# MX4-7-9.net
KiCad netlist of a schematic drawn in EAGLE
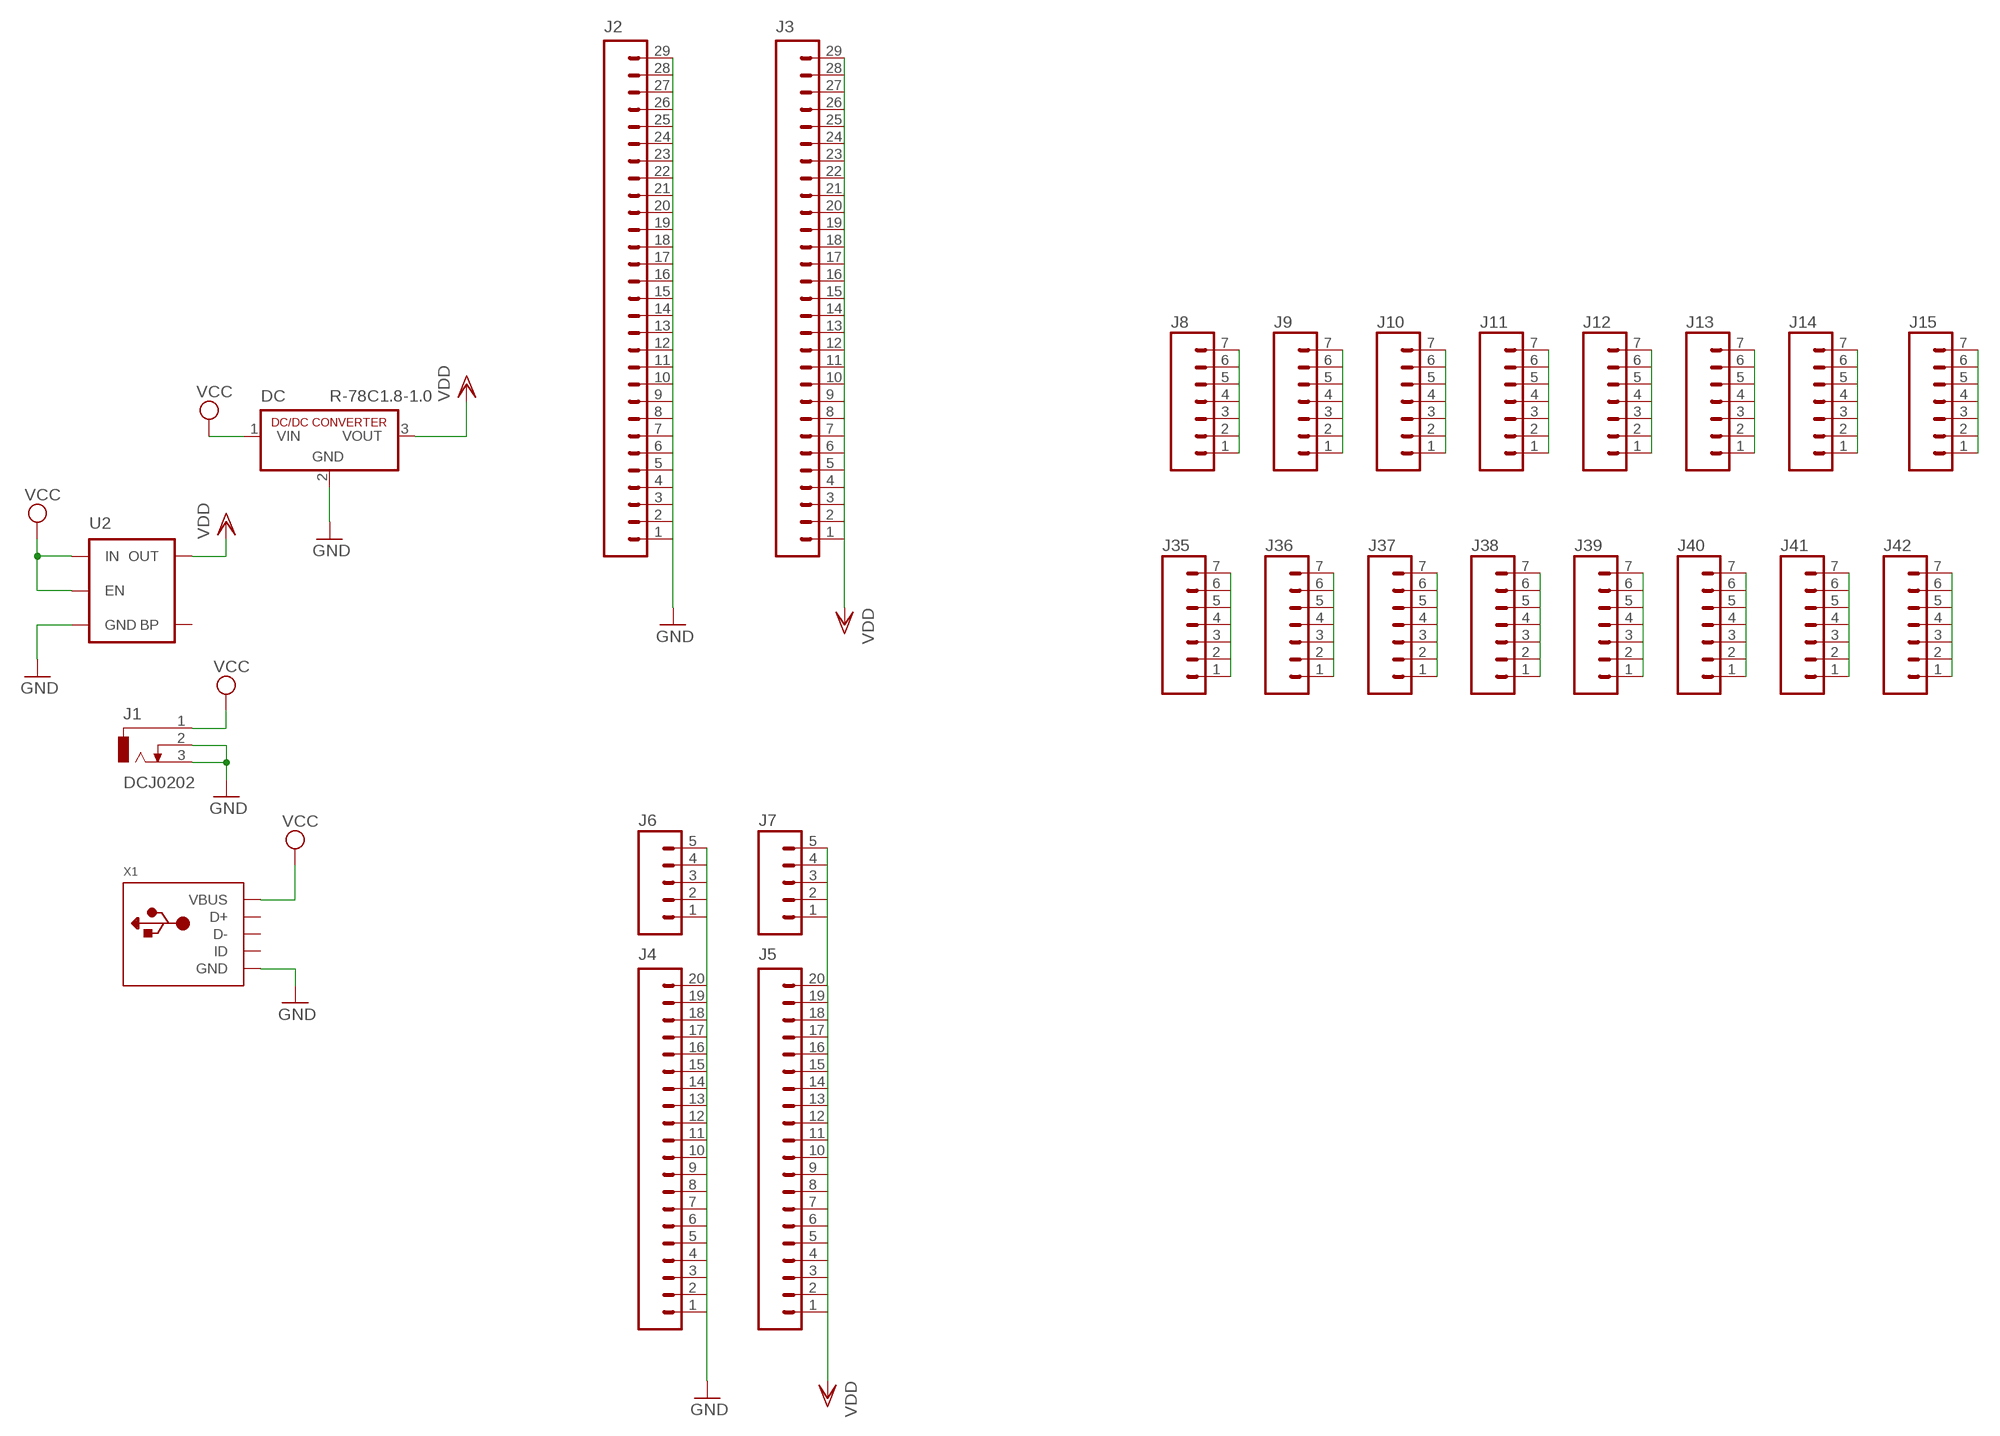
[diagram p0: schematic, sheet 1, part 1 of 2]
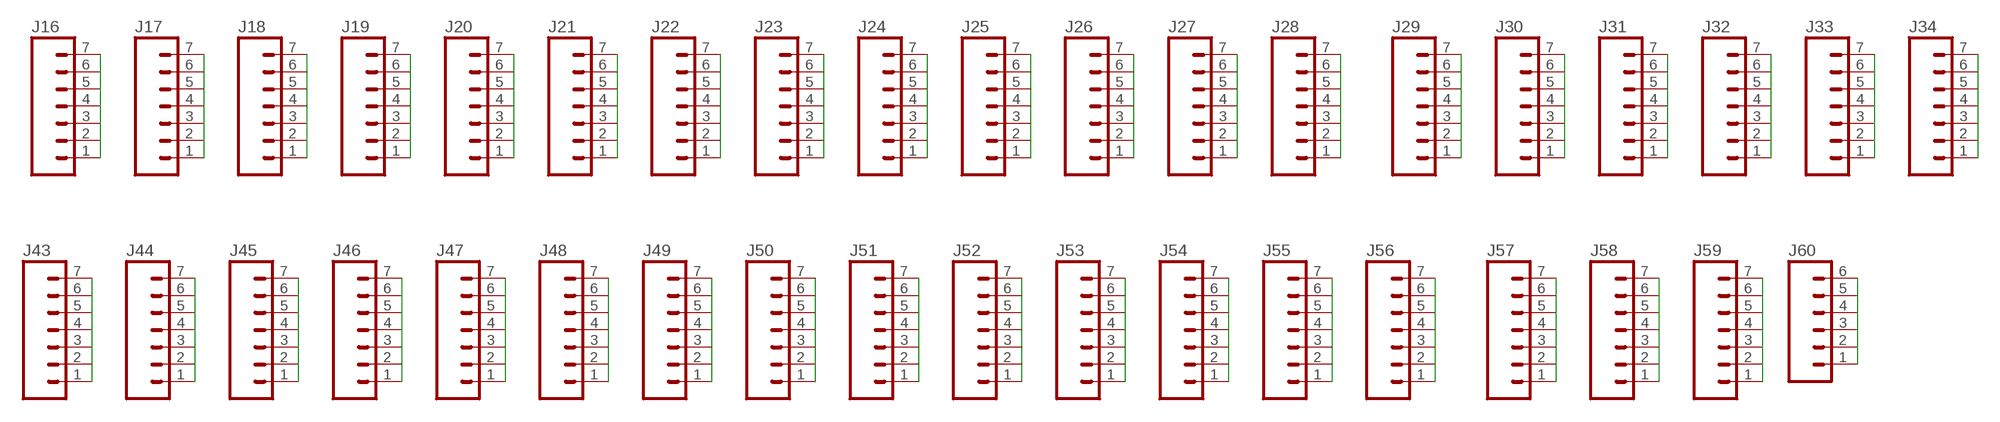
[diagram p1: schematic, sheet 1, part 2 of 2]

(export (version "E")
  (design (tool "Eeschema 10.0.6"))
  (components
    (comp (ref "DC")
      (value "R-78C1.8-1.0")
      (footprint "eagle-import:SIP3")
      (libsource (lib "eagle-import") (part "R-78C-1.01.8"))
    )
    (comp (ref "J1")
      (value "DCJ0202")
      (footprint "eagle-import:DCJ0202")
      (libsource (lib "eagle-import") (part "DCJ0202"))
    )
    (comp (ref "J2")
      (value "M29NO_SILK")
      (footprint "eagle-import:1X29_NO_SILK")
      (libsource (lib "eagle-import") (part "M29NO_SILK"))
    )
    (comp (ref "J3")
      (value "M29NO_SILK")
      (footprint "eagle-import:1X29_NO_SILK")
      (libsource (lib "eagle-import") (part "M29NO_SILK"))
    )
    (comp (ref "J4")
      (value "M20NO_SILK_KIT")
      (footprint "eagle-import:1X20_NO_SILK_KIT")
      (libsource (lib "eagle-import") (part "M20NO_SILK_KIT"))
    )
    (comp (ref "J5")
      (value "M20NO_SILK_KIT")
      (footprint "eagle-import:1X20_NO_SILK_KIT")
      (libsource (lib "eagle-import") (part "M20NO_SILK_KIT"))
    )
    (comp (ref "J6")
      (value "M05NO_SILK")
      (footprint "eagle-import:1X05_NO_SILK")
      (libsource (lib "eagle-import") (part "M05NO_SILK"))
    )
    (comp (ref "J7")
      (value "M05NO_SILK")
      (footprint "eagle-import:1X05_NO_SILK")
      (libsource (lib "eagle-import") (part "M05NO_SILK"))
    )
    (comp (ref "J8")
      (value "M07NO_SILK")
      (footprint "eagle-import:1X07_NO_SILK")
      (libsource (lib "eagle-import") (part "M07NO_SILK"))
    )
    (comp (ref "J9")
      (value "M07NO_SILK")
      (footprint "eagle-import:1X07_NO_SILK")
      (libsource (lib "eagle-import") (part "M07NO_SILK"))
    )
    (comp (ref "J10")
      (value "M07NO_SILK")
      (footprint "eagle-import:1X07_NO_SILK")
      (libsource (lib "eagle-import") (part "M07NO_SILK"))
    )
    (comp (ref "J11")
      (value "M07NO_SILK")
      (footprint "eagle-import:1X07_NO_SILK")
      (libsource (lib "eagle-import") (part "M07NO_SILK"))
    )
    (comp (ref "J12")
      (value "M07NO_SILK")
      (footprint "eagle-import:1X07_NO_SILK")
      (libsource (lib "eagle-import") (part "M07NO_SILK"))
    )
    (comp (ref "J13")
      (value "M07NO_SILK")
      (footprint "eagle-import:1X07_NO_SILK")
      (libsource (lib "eagle-import") (part "M07NO_SILK"))
    )
    (comp (ref "J14")
      (value "M07NO_SILK")
      (footprint "eagle-import:1X07_NO_SILK")
      (libsource (lib "eagle-import") (part "M07NO_SILK"))
    )
    (comp (ref "J15")
      (value "M07NO_SILK")
      (footprint "eagle-import:1X07_NO_SILK")
      (libsource (lib "eagle-import") (part "M07NO_SILK"))
    )
    (comp (ref "J16")
      (value "M07NO_SILK")
      (footprint "eagle-import:1X07_NO_SILK")
      (libsource (lib "eagle-import") (part "M07NO_SILK"))
    )
    (comp (ref "J17")
      (value "M07NO_SILK")
      (footprint "eagle-import:1X07_NO_SILK")
      (libsource (lib "eagle-import") (part "M07NO_SILK"))
    )
    (comp (ref "J18")
      (value "M07NO_SILK")
      (footprint "eagle-import:1X07_NO_SILK")
      (libsource (lib "eagle-import") (part "M07NO_SILK"))
    )
    (comp (ref "J19")
      (value "M07NO_SILK")
      (footprint "eagle-import:1X07_NO_SILK")
      (libsource (lib "eagle-import") (part "M07NO_SILK"))
    )
    (comp (ref "J20")
      (value "M07NO_SILK")
      (footprint "eagle-import:1X07_NO_SILK")
      (libsource (lib "eagle-import") (part "M07NO_SILK"))
    )
    (comp (ref "J21")
      (value "M07NO_SILK")
      (footprint "eagle-import:1X07_NO_SILK")
      (libsource (lib "eagle-import") (part "M07NO_SILK"))
    )
    (comp (ref "J22")
      (value "M07NO_SILK")
      (footprint "eagle-import:1X07_NO_SILK")
      (libsource (lib "eagle-import") (part "M07NO_SILK"))
    )
    (comp (ref "J23")
      (value "M07NO_SILK")
      (footprint "eagle-import:1X07_NO_SILK")
      (libsource (lib "eagle-import") (part "M07NO_SILK"))
    )
    (comp (ref "J24")
      (value "M07NO_SILK")
      (footprint "eagle-import:1X07_NO_SILK")
      (libsource (lib "eagle-import") (part "M07NO_SILK"))
    )
    (comp (ref "J25")
      (value "M07NO_SILK")
      (footprint "eagle-import:1X07_NO_SILK")
      (libsource (lib "eagle-import") (part "M07NO_SILK"))
    )
    (comp (ref "J26")
      (value "M07NO_SILK")
      (footprint "eagle-import:1X07_NO_SILK")
      (libsource (lib "eagle-import") (part "M07NO_SILK"))
    )
    (comp (ref "J27")
      (value "M07NO_SILK")
      (footprint "eagle-import:1X07_NO_SILK")
      (libsource (lib "eagle-import") (part "M07NO_SILK"))
    )
    (comp (ref "J28")
      (value "M07NO_SILK")
      (footprint "eagle-import:1X07_NO_SILK")
      (libsource (lib "eagle-import") (part "M07NO_SILK"))
    )
    (comp (ref "J29")
      (value "M07NO_SILK")
      (footprint "eagle-import:1X07_NO_SILK")
      (libsource (lib "eagle-import") (part "M07NO_SILK"))
    )
    (comp (ref "J30")
      (value "M07NO_SILK")
      (footprint "eagle-import:1X07_NO_SILK")
      (libsource (lib "eagle-import") (part "M07NO_SILK"))
    )
    (comp (ref "J31")
      (value "M07NO_SILK")
      (footprint "eagle-import:1X07_NO_SILK")
      (libsource (lib "eagle-import") (part "M07NO_SILK"))
    )
    (comp (ref "J32")
      (value "M07NO_SILK")
      (footprint "eagle-import:1X07_NO_SILK")
      (libsource (lib "eagle-import") (part "M07NO_SILK"))
    )
    (comp (ref "J33")
      (value "M07NO_SILK")
      (footprint "eagle-import:1X07_NO_SILK")
      (libsource (lib "eagle-import") (part "M07NO_SILK"))
    )
    (comp (ref "J34")
      (value "M07NO_SILK")
      (footprint "eagle-import:1X07_NO_SILK")
      (libsource (lib "eagle-import") (part "M07NO_SILK"))
    )
    (comp (ref "J35")
      (value "M07NO_SILK")
      (footprint "eagle-import:1X07_NO_SILK")
      (libsource (lib "eagle-import") (part "M07NO_SILK"))
    )
    (comp (ref "J36")
      (value "M07NO_SILK")
      (footprint "eagle-import:1X07_NO_SILK")
      (libsource (lib "eagle-import") (part "M07NO_SILK"))
    )
    (comp (ref "J37")
      (value "M07NO_SILK")
      (footprint "eagle-import:1X07_NO_SILK")
      (libsource (lib "eagle-import") (part "M07NO_SILK"))
    )
    (comp (ref "J38")
      (value "M07NO_SILK")
      (footprint "eagle-import:1X07_NO_SILK")
      (libsource (lib "eagle-import") (part "M07NO_SILK"))
    )
    (comp (ref "J39")
      (value "M07NO_SILK")
      (footprint "eagle-import:1X07_NO_SILK")
      (libsource (lib "eagle-import") (part "M07NO_SILK"))
    )
    (comp (ref "J40")
      (value "M07NO_SILK")
      (footprint "eagle-import:1X07_NO_SILK")
      (libsource (lib "eagle-import") (part "M07NO_SILK"))
    )
    (comp (ref "J41")
      (value "M07NO_SILK")
      (footprint "eagle-import:1X07_NO_SILK")
      (libsource (lib "eagle-import") (part "M07NO_SILK"))
    )
    (comp (ref "J42")
      (value "M07NO_SILK")
      (footprint "eagle-import:1X07_NO_SILK")
      (libsource (lib "eagle-import") (part "M07NO_SILK"))
    )
    (comp (ref "J43")
      (value "M07NO_SILK")
      (footprint "eagle-import:1X07_NO_SILK")
      (libsource (lib "eagle-import") (part "M07NO_SILK"))
    )
    (comp (ref "J44")
      (value "M07NO_SILK")
      (footprint "eagle-import:1X07_NO_SILK")
      (libsource (lib "eagle-import") (part "M07NO_SILK"))
    )
    (comp (ref "J45")
      (value "M07NO_SILK")
      (footprint "eagle-import:1X07_NO_SILK")
      (libsource (lib "eagle-import") (part "M07NO_SILK"))
    )
    (comp (ref "J46")
      (value "M07NO_SILK")
      (footprint "eagle-import:1X07_NO_SILK")
      (libsource (lib "eagle-import") (part "M07NO_SILK"))
    )
    (comp (ref "J47")
      (value "M07NO_SILK")
      (footprint "eagle-import:1X07_NO_SILK")
      (libsource (lib "eagle-import") (part "M07NO_SILK"))
    )
    (comp (ref "J48")
      (value "M07NO_SILK")
      (footprint "eagle-import:1X07_NO_SILK")
      (libsource (lib "eagle-import") (part "M07NO_SILK"))
    )
    (comp (ref "J49")
      (value "M07NO_SILK")
      (footprint "eagle-import:1X07_NO_SILK")
      (libsource (lib "eagle-import") (part "M07NO_SILK"))
    )
    (comp (ref "J50")
      (value "M07NO_SILK")
      (footprint "eagle-import:1X07_NO_SILK")
      (libsource (lib "eagle-import") (part "M07NO_SILK"))
    )
    (comp (ref "J51")
      (value "M07NO_SILK")
      (footprint "eagle-import:1X07_NO_SILK")
      (libsource (lib "eagle-import") (part "M07NO_SILK"))
    )
    (comp (ref "J52")
      (value "M07NO_SILK")
      (footprint "eagle-import:1X07_NO_SILK")
      (libsource (lib "eagle-import") (part "M07NO_SILK"))
    )
    (comp (ref "J53")
      (value "M07NO_SILK")
      (footprint "eagle-import:1X07_NO_SILK")
      (libsource (lib "eagle-import") (part "M07NO_SILK"))
    )
    (comp (ref "J54")
      (value "M07NO_SILK")
      (footprint "eagle-import:1X07_NO_SILK")
      (libsource (lib "eagle-import") (part "M07NO_SILK"))
    )
    (comp (ref "J55")
      (value "M07NO_SILK")
      (footprint "eagle-import:1X07_NO_SILK")
      (libsource (lib "eagle-import") (part "M07NO_SILK"))
    )
    (comp (ref "J56")
      (value "M07NO_SILK")
      (footprint "eagle-import:1X07_NO_SILK")
      (libsource (lib "eagle-import") (part "M07NO_SILK"))
    )
    (comp (ref "J57")
      (value "M07NO_SILK")
      (footprint "eagle-import:1X07_NO_SILK")
      (libsource (lib "eagle-import") (part "M07NO_SILK"))
    )
    (comp (ref "J58")
      (value "M07NO_SILK")
      (footprint "eagle-import:1X07_NO_SILK")
      (libsource (lib "eagle-import") (part "M07NO_SILK"))
    )
    (comp (ref "J59")
      (value "M07NO_SILK")
      (footprint "eagle-import:1X07_NO_SILK")
      (libsource (lib "eagle-import") (part "M07NO_SILK"))
    )
    (comp (ref "J60")
      (value "M06NO_SILK_FEMALE_PTH")
      (footprint "eagle-import:1X06_NO_SILK")
      (libsource (lib "eagle-import") (part "M06NO_SILK_FEMALE_PTH"))
    )
    (comp (ref "U2")
      (value "MIC52053.3V")
      (footprint "eagle-import:SOT23-5")
      (libsource (lib "eagle-import") (part "MIC52053.3V"))
    )
    (comp (ref "X1")
      (value "USBMICRO_20329")
      (footprint "eagle-import:4UCONN_20329")
      (libsource (lib "eagle-import") (part "USBMICRO_20329"))
    )
  )
  (nets
    (net (code "1") (name "GND") (class "Default")
      (node (ref "DC") (pin "2") (pinfunction "GND_2") (pintype "passive"))
      (node (ref "J1") (pin "2") (pinfunction "2_2") (pintype "passive"))
      (node (ref "J1") (pin "3") (pinfunction "3_3") (pintype "passive"))
      (node (ref "J2") (pin "1") (pinfunction "1_1") (pintype "passive"))
      (node (ref "J2") (pin "10") (pinfunction "10_10") (pintype "passive"))
      (node (ref "J2") (pin "11") (pinfunction "11_11") (pintype "passive"))
      (node (ref "J2") (pin "12") (pinfunction "12_12") (pintype "passive"))
      (node (ref "J2") (pin "13") (pinfunction "13_13") (pintype "passive"))
      (node (ref "J2") (pin "14") (pinfunction "14_14") (pintype "passive"))
      (node (ref "J2") (pin "15") (pinfunction "15_15") (pintype "passive"))
      (node (ref "J2") (pin "16") (pinfunction "16_16") (pintype "passive"))
      (node (ref "J2") (pin "17") (pinfunction "17_17") (pintype "passive"))
      (node (ref "J2") (pin "18") (pinfunction "18_18") (pintype "passive"))
      (node (ref "J2") (pin "19") (pinfunction "19_19") (pintype "passive"))
      (node (ref "J2") (pin "2") (pinfunction "2_2") (pintype "passive"))
      (node (ref "J2") (pin "20") (pinfunction "20_20") (pintype "passive"))
      (node (ref "J2") (pin "21") (pinfunction "21_21") (pintype "passive"))
      (node (ref "J2") (pin "22") (pinfunction "22_22") (pintype "passive"))
      (node (ref "J2") (pin "23") (pinfunction "23_23") (pintype "passive"))
      (node (ref "J2") (pin "24") (pinfunction "24_24") (pintype "passive"))
      (node (ref "J2") (pin "25") (pinfunction "25_25") (pintype "passive"))
      (node (ref "J2") (pin "26") (pinfunction "26_26") (pintype "passive"))
      (node (ref "J2") (pin "27") (pinfunction "27_27") (pintype "passive"))
      (node (ref "J2") (pin "28") (pinfunction "28_28") (pintype "passive"))
      (node (ref "J2") (pin "29") (pinfunction "29_29") (pintype "passive"))
      (node (ref "J2") (pin "3") (pinfunction "3_3") (pintype "passive"))
      (node (ref "J2") (pin "4") (pinfunction "4_4") (pintype "passive"))
      (node (ref "J2") (pin "5") (pinfunction "5_5") (pintype "passive"))
      (node (ref "J2") (pin "6") (pinfunction "6_6") (pintype "passive"))
      (node (ref "J2") (pin "7") (pinfunction "7_7") (pintype "passive"))
      (node (ref "J2") (pin "8") (pinfunction "8_8") (pintype "passive"))
      (node (ref "J2") (pin "9") (pinfunction "9_9") (pintype "passive"))
      (node (ref "J4") (pin "1") (pinfunction "1_1") (pintype "passive"))
      (node (ref "J4") (pin "10") (pinfunction "10_10") (pintype "passive"))
      (node (ref "J4") (pin "11") (pinfunction "11_11") (pintype "passive"))
      (node (ref "J4") (pin "12") (pinfunction "12_12") (pintype "passive"))
      (node (ref "J4") (pin "13") (pinfunction "13_13") (pintype "passive"))
      (node (ref "J4") (pin "14") (pinfunction "14_14") (pintype "passive"))
      (node (ref "J4") (pin "15") (pinfunction "15_15") (pintype "passive"))
      (node (ref "J4") (pin "16") (pinfunction "16_16") (pintype "passive"))
      (node (ref "J4") (pin "17") (pinfunction "17_17") (pintype "passive"))
      (node (ref "J4") (pin "18") (pinfunction "18_18") (pintype "passive"))
      (node (ref "J4") (pin "19") (pinfunction "19_19") (pintype "passive"))
      (node (ref "J4") (pin "2") (pinfunction "2_2") (pintype "passive"))
      (node (ref "J4") (pin "20") (pinfunction "20_20") (pintype "passive"))
      (node (ref "J4") (pin "3") (pinfunction "3_3") (pintype "passive"))
      (node (ref "J4") (pin "4") (pinfunction "4_4") (pintype "passive"))
      (node (ref "J4") (pin "5") (pinfunction "5_5") (pintype "passive"))
      (node (ref "J4") (pin "6") (pinfunction "6_6") (pintype "passive"))
      (node (ref "J4") (pin "7") (pinfunction "7_7") (pintype "passive"))
      (node (ref "J4") (pin "8") (pinfunction "8_8") (pintype "passive"))
      (node (ref "J4") (pin "9") (pinfunction "9_9") (pintype "passive"))
      (node (ref "J6") (pin "1") (pinfunction "1_1") (pintype "passive"))
      (node (ref "J6") (pin "2") (pinfunction "2_2") (pintype "passive"))
      (node (ref "J6") (pin "3") (pinfunction "3_3") (pintype "passive"))
      (node (ref "J6") (pin "4") (pinfunction "4_4") (pintype "passive"))
      (node (ref "J6") (pin "5") (pinfunction "5_5") (pintype "passive"))
      (node (ref "U2") (pin "2") (pinfunction "GND_2") (pintype "input"))
      (node (ref "X1") (pin "BASE@1") (pinfunction "GND_BASE@1") (pintype "power_in"))
      (node (ref "X1") (pin "BASE@2") (pinfunction "GND_BASE@2") (pintype "power_in"))
      (node (ref "X1") (pin "GND") (pinfunction "GND_GND") (pintype "power_in"))
      (node (ref "X1") (pin "SPRT@1") (pinfunction "GND_SPRT@1") (pintype "power_in"))
      (node (ref "X1") (pin "SPRT@2") (pinfunction "GND_SPRT@2") (pintype "power_in"))
      (node (ref "X1") (pin "SPRT@3") (pinfunction "GND_SPRT@3") (pintype "power_in"))
      (node (ref "X1") (pin "SPRT@4") (pinfunction "GND_SPRT@4") (pintype "power_in"))
    )
    (net (code "2") (name "Net-(J8-Pad1)") (class "Default")
      (node (ref "J8") (pin "1") (pinfunction "1_1") (pintype "passive"))
      (node (ref "J8") (pin "2") (pinfunction "2_2") (pintype "passive"))
      (node (ref "J8") (pin "3") (pinfunction "3_3") (pintype "passive"))
      (node (ref "J8") (pin "4") (pinfunction "4_4") (pintype "passive"))
      (node (ref "J8") (pin "5") (pinfunction "5_5") (pintype "passive"))
      (node (ref "J8") (pin "6") (pinfunction "6_6") (pintype "passive"))
      (node (ref "J8") (pin "7") (pinfunction "7_7") (pintype "passive"))
    )
    (net (code "3") (name "Net-(J9-Pad1)") (class "Default")
      (node (ref "J9") (pin "1") (pinfunction "1_1") (pintype "passive"))
      (node (ref "J9") (pin "2") (pinfunction "2_2") (pintype "passive"))
      (node (ref "J9") (pin "3") (pinfunction "3_3") (pintype "passive"))
      (node (ref "J9") (pin "4") (pinfunction "4_4") (pintype "passive"))
      (node (ref "J9") (pin "5") (pinfunction "5_5") (pintype "passive"))
      (node (ref "J9") (pin "6") (pinfunction "6_6") (pintype "passive"))
      (node (ref "J9") (pin "7") (pinfunction "7_7") (pintype "passive"))
    )
    (net (code "4") (name "Net-(J10-Pad1)") (class "Default")
      (node (ref "J10") (pin "1") (pinfunction "1_1") (pintype "passive"))
      (node (ref "J10") (pin "2") (pinfunction "2_2") (pintype "passive"))
      (node (ref "J10") (pin "3") (pinfunction "3_3") (pintype "passive"))
      (node (ref "J10") (pin "4") (pinfunction "4_4") (pintype "passive"))
      (node (ref "J10") (pin "5") (pinfunction "5_5") (pintype "passive"))
      (node (ref "J10") (pin "6") (pinfunction "6_6") (pintype "passive"))
      (node (ref "J10") (pin "7") (pinfunction "7_7") (pintype "passive"))
    )
    (net (code "5") (name "Net-(J11-Pad1)") (class "Default")
      (node (ref "J11") (pin "1") (pinfunction "1_1") (pintype "passive"))
      (node (ref "J11") (pin "2") (pinfunction "2_2") (pintype "passive"))
      (node (ref "J11") (pin "3") (pinfunction "3_3") (pintype "passive"))
      (node (ref "J11") (pin "4") (pinfunction "4_4") (pintype "passive"))
      (node (ref "J11") (pin "5") (pinfunction "5_5") (pintype "passive"))
      (node (ref "J11") (pin "6") (pinfunction "6_6") (pintype "passive"))
      (node (ref "J11") (pin "7") (pinfunction "7_7") (pintype "passive"))
    )
    (net (code "6") (name "Net-(J12-Pad1)") (class "Default")
      (node (ref "J12") (pin "1") (pinfunction "1_1") (pintype "passive"))
      (node (ref "J12") (pin "2") (pinfunction "2_2") (pintype "passive"))
      (node (ref "J12") (pin "3") (pinfunction "3_3") (pintype "passive"))
      (node (ref "J12") (pin "4") (pinfunction "4_4") (pintype "passive"))
      (node (ref "J12") (pin "5") (pinfunction "5_5") (pintype "passive"))
      (node (ref "J12") (pin "6") (pinfunction "6_6") (pintype "passive"))
      (node (ref "J12") (pin "7") (pinfunction "7_7") (pintype "passive"))
    )
    (net (code "7") (name "Net-(J13-Pad1)") (class "Default")
      (node (ref "J13") (pin "1") (pinfunction "1_1") (pintype "passive"))
      (node (ref "J13") (pin "2") (pinfunction "2_2") (pintype "passive"))
      (node (ref "J13") (pin "3") (pinfunction "3_3") (pintype "passive"))
      (node (ref "J13") (pin "4") (pinfunction "4_4") (pintype "passive"))
      (node (ref "J13") (pin "5") (pinfunction "5_5") (pintype "passive"))
      (node (ref "J13") (pin "6") (pinfunction "6_6") (pintype "passive"))
      (node (ref "J13") (pin "7") (pinfunction "7_7") (pintype "passive"))
    )
    (net (code "8") (name "Net-(J14-Pad1)") (class "Default")
      (node (ref "J14") (pin "1") (pinfunction "1_1") (pintype "passive"))
      (node (ref "J14") (pin "2") (pinfunction "2_2") (pintype "passive"))
      (node (ref "J14") (pin "3") (pinfunction "3_3") (pintype "passive"))
      (node (ref "J14") (pin "4") (pinfunction "4_4") (pintype "passive"))
      (node (ref "J14") (pin "5") (pinfunction "5_5") (pintype "passive"))
      (node (ref "J14") (pin "6") (pinfunction "6_6") (pintype "passive"))
      (node (ref "J14") (pin "7") (pinfunction "7_7") (pintype "passive"))
    )
    (net (code "9") (name "Net-(J15-Pad1)") (class "Default")
      (node (ref "J15") (pin "1") (pinfunction "1_1") (pintype "passive"))
      (node (ref "J15") (pin "2") (pinfunction "2_2") (pintype "passive"))
      (node (ref "J15") (pin "3") (pinfunction "3_3") (pintype "passive"))
      (node (ref "J15") (pin "4") (pinfunction "4_4") (pintype "passive"))
      (node (ref "J15") (pin "5") (pinfunction "5_5") (pintype "passive"))
      (node (ref "J15") (pin "6") (pinfunction "6_6") (pintype "passive"))
      (node (ref "J15") (pin "7") (pinfunction "7_7") (pintype "passive"))
    )
    (net (code "10") (name "Net-(J16-Pad1)") (class "Default")
      (node (ref "J16") (pin "1") (pinfunction "1_1") (pintype "passive"))
      (node (ref "J16") (pin "2") (pinfunction "2_2") (pintype "passive"))
      (node (ref "J16") (pin "3") (pinfunction "3_3") (pintype "passive"))
      (node (ref "J16") (pin "4") (pinfunction "4_4") (pintype "passive"))
      (node (ref "J16") (pin "5") (pinfunction "5_5") (pintype "passive"))
      (node (ref "J16") (pin "6") (pinfunction "6_6") (pintype "passive"))
      (node (ref "J16") (pin "7") (pinfunction "7_7") (pintype "passive"))
    )
    (net (code "11") (name "Net-(J17-Pad1)") (class "Default")
      (node (ref "J17") (pin "1") (pinfunction "1_1") (pintype "passive"))
      (node (ref "J17") (pin "2") (pinfunction "2_2") (pintype "passive"))
      (node (ref "J17") (pin "3") (pinfunction "3_3") (pintype "passive"))
      (node (ref "J17") (pin "4") (pinfunction "4_4") (pintype "passive"))
      (node (ref "J17") (pin "5") (pinfunction "5_5") (pintype "passive"))
      (node (ref "J17") (pin "6") (pinfunction "6_6") (pintype "passive"))
      (node (ref "J17") (pin "7") (pinfunction "7_7") (pintype "passive"))
    )
    (net (code "12") (name "Net-(J18-Pad1)") (class "Default")
      (node (ref "J18") (pin "1") (pinfunction "1_1") (pintype "passive"))
      (node (ref "J18") (pin "2") (pinfunction "2_2") (pintype "passive"))
      (node (ref "J18") (pin "3") (pinfunction "3_3") (pintype "passive"))
      (node (ref "J18") (pin "4") (pinfunction "4_4") (pintype "passive"))
      (node (ref "J18") (pin "5") (pinfunction "5_5") (pintype "passive"))
      (node (ref "J18") (pin "6") (pinfunction "6_6") (pintype "passive"))
      (node (ref "J18") (pin "7") (pinfunction "7_7") (pintype "passive"))
    )
    (net (code "13") (name "Net-(J19-Pad1)") (class "Default")
      (node (ref "J19") (pin "1") (pinfunction "1_1") (pintype "passive"))
      (node (ref "J19") (pin "2") (pinfunction "2_2") (pintype "passive"))
      (node (ref "J19") (pin "3") (pinfunction "3_3") (pintype "passive"))
      (node (ref "J19") (pin "4") (pinfunction "4_4") (pintype "passive"))
      (node (ref "J19") (pin "5") (pinfunction "5_5") (pintype "passive"))
      (node (ref "J19") (pin "6") (pinfunction "6_6") (pintype "passive"))
      (node (ref "J19") (pin "7") (pinfunction "7_7") (pintype "passive"))
    )
    (net (code "14") (name "Net-(J20-Pad1)") (class "Default")
      (node (ref "J20") (pin "1") (pinfunction "1_1") (pintype "passive"))
      (node (ref "J20") (pin "2") (pinfunction "2_2") (pintype "passive"))
      (node (ref "J20") (pin "3") (pinfunction "3_3") (pintype "passive"))
      (node (ref "J20") (pin "4") (pinfunction "4_4") (pintype "passive"))
      (node (ref "J20") (pin "5") (pinfunction "5_5") (pintype "passive"))
      (node (ref "J20") (pin "6") (pinfunction "6_6") (pintype "passive"))
      (node (ref "J20") (pin "7") (pinfunction "7_7") (pintype "passive"))
    )
    (net (code "15") (name "Net-(J21-Pad1)") (class "Default")
      (node (ref "J21") (pin "1") (pinfunction "1_1") (pintype "passive"))
      (node (ref "J21") (pin "2") (pinfunction "2_2") (pintype "passive"))
      (node (ref "J21") (pin "3") (pinfunction "3_3") (pintype "passive"))
      (node (ref "J21") (pin "4") (pinfunction "4_4") (pintype "passive"))
      (node (ref "J21") (pin "5") (pinfunction "5_5") (pintype "passive"))
      (node (ref "J21") (pin "6") (pinfunction "6_6") (pintype "passive"))
      (node (ref "J21") (pin "7") (pinfunction "7_7") (pintype "passive"))
    )
    (net (code "16") (name "Net-(J22-Pad1)") (class "Default")
      (node (ref "J22") (pin "1") (pinfunction "1_1") (pintype "passive"))
      (node (ref "J22") (pin "2") (pinfunction "2_2") (pintype "passive"))
      (node (ref "J22") (pin "3") (pinfunction "3_3") (pintype "passive"))
      (node (ref "J22") (pin "4") (pinfunction "4_4") (pintype "passive"))
      (node (ref "J22") (pin "5") (pinfunction "5_5") (pintype "passive"))
      (node (ref "J22") (pin "6") (pinfunction "6_6") (pintype "passive"))
      (node (ref "J22") (pin "7") (pinfunction "7_7") (pintype "passive"))
    )
    (net (code "17") (name "Net-(J23-Pad1)") (class "Default")
      (node (ref "J23") (pin "1") (pinfunction "1_1") (pintype "passive"))
      (node (ref "J23") (pin "2") (pinfunction "2_2") (pintype "passive"))
      (node (ref "J23") (pin "3") (pinfunction "3_3") (pintype "passive"))
      (node (ref "J23") (pin "4") (pinfunction "4_4") (pintype "passive"))
      (node (ref "J23") (pin "5") (pinfunction "5_5") (pintype "passive"))
      (node (ref "J23") (pin "6") (pinfunction "6_6") (pintype "passive"))
      (node (ref "J23") (pin "7") (pinfunction "7_7") (pintype "passive"))
    )
    (net (code "18") (name "Net-(J24-Pad1)") (class "Default")
      (node (ref "J24") (pin "1") (pinfunction "1_1") (pintype "passive"))
      (node (ref "J24") (pin "2") (pinfunction "2_2") (pintype "passive"))
      (node (ref "J24") (pin "3") (pinfunction "3_3") (pintype "passive"))
      (node (ref "J24") (pin "4") (pinfunction "4_4") (pintype "passive"))
      (node (ref "J24") (pin "5") (pinfunction "5_5") (pintype "passive"))
      (node (ref "J24") (pin "6") (pinfunction "6_6") (pintype "passive"))
      (node (ref "J24") (pin "7") (pinfunction "7_7") (pintype "passive"))
    )
    (net (code "19") (name "Net-(J25-Pad1)") (class "Default")
      (node (ref "J25") (pin "1") (pinfunction "1_1") (pintype "passive"))
      (node (ref "J25") (pin "2") (pinfunction "2_2") (pintype "passive"))
      (node (ref "J25") (pin "3") (pinfunction "3_3") (pintype "passive"))
      (node (ref "J25") (pin "4") (pinfunction "4_4") (pintype "passive"))
      (node (ref "J25") (pin "5") (pinfunction "5_5") (pintype "passive"))
      (node (ref "J25") (pin "6") (pinfunction "6_6") (pintype "passive"))
      (node (ref "J25") (pin "7") (pinfunction "7_7") (pintype "passive"))
    )
    (net (code "20") (name "Net-(J26-Pad1)") (class "Default")
      (node (ref "J26") (pin "1") (pinfunction "1_1") (pintype "passive"))
      (node (ref "J26") (pin "2") (pinfunction "2_2") (pintype "passive"))
      (node (ref "J26") (pin "3") (pinfunction "3_3") (pintype "passive"))
      (node (ref "J26") (pin "4") (pinfunction "4_4") (pintype "passive"))
      (node (ref "J26") (pin "5") (pinfunction "5_5") (pintype "passive"))
      (node (ref "J26") (pin "6") (pinfunction "6_6") (pintype "passive"))
      (node (ref "J26") (pin "7") (pinfunction "7_7") (pintype "passive"))
    )
    (net (code "21") (name "Net-(J27-Pad1)") (class "Default")
      (node (ref "J27") (pin "1") (pinfunction "1_1") (pintype "passive"))
      (node (ref "J27") (pin "2") (pinfunction "2_2") (pintype "passive"))
      (node (ref "J27") (pin "3") (pinfunction "3_3") (pintype "passive"))
      (node (ref "J27") (pin "4") (pinfunction "4_4") (pintype "passive"))
      (node (ref "J27") (pin "5") (pinfunction "5_5") (pintype "passive"))
      (node (ref "J27") (pin "6") (pinfunction "6_6") (pintype "passive"))
      (node (ref "J27") (pin "7") (pinfunction "7_7") (pintype "passive"))
    )
    (net (code "22") (name "Net-(J28-Pad1)") (class "Default")
      (node (ref "J28") (pin "1") (pinfunction "1_1") (pintype "passive"))
      (node (ref "J28") (pin "2") (pinfunction "2_2") (pintype "passive"))
      (node (ref "J28") (pin "3") (pinfunction "3_3") (pintype "passive"))
      (node (ref "J28") (pin "4") (pinfunction "4_4") (pintype "passive"))
      (node (ref "J28") (pin "5") (pinfunction "5_5") (pintype "passive"))
      (node (ref "J28") (pin "6") (pinfunction "6_6") (pintype "passive"))
      (node (ref "J28") (pin "7") (pinfunction "7_7") (pintype "passive"))
    )
    (net (code "23") (name "Net-(J29-Pad1)") (class "Default")
      (node (ref "J29") (pin "1") (pinfunction "1_1") (pintype "passive"))
      (node (ref "J29") (pin "2") (pinfunction "2_2") (pintype "passive"))
      (node (ref "J29") (pin "3") (pinfunction "3_3") (pintype "passive"))
      (node (ref "J29") (pin "4") (pinfunction "4_4") (pintype "passive"))
      (node (ref "J29") (pin "5") (pinfunction "5_5") (pintype "passive"))
      (node (ref "J29") (pin "6") (pinfunction "6_6") (pintype "passive"))
      (node (ref "J29") (pin "7") (pinfunction "7_7") (pintype "passive"))
    )
    (net (code "24") (name "Net-(J30-Pad1)") (class "Default")
      (node (ref "J30") (pin "1") (pinfunction "1_1") (pintype "passive"))
      (node (ref "J30") (pin "2") (pinfunction "2_2") (pintype "passive"))
      (node (ref "J30") (pin "3") (pinfunction "3_3") (pintype "passive"))
      (node (ref "J30") (pin "4") (pinfunction "4_4") (pintype "passive"))
      (node (ref "J30") (pin "5") (pinfunction "5_5") (pintype "passive"))
      (node (ref "J30") (pin "6") (pinfunction "6_6") (pintype "passive"))
      (node (ref "J30") (pin "7") (pinfunction "7_7") (pintype "passive"))
    )
    (net (code "25") (name "Net-(J31-Pad1)") (class "Default")
      (node (ref "J31") (pin "1") (pinfunction "1_1") (pintype "passive"))
      (node (ref "J31") (pin "2") (pinfunction "2_2") (pintype "passive"))
      (node (ref "J31") (pin "3") (pinfunction "3_3") (pintype "passive"))
      (node (ref "J31") (pin "4") (pinfunction "4_4") (pintype "passive"))
      (node (ref "J31") (pin "5") (pinfunction "5_5") (pintype "passive"))
      (node (ref "J31") (pin "6") (pinfunction "6_6") (pintype "passive"))
      (node (ref "J31") (pin "7") (pinfunction "7_7") (pintype "passive"))
    )
    (net (code "26") (name "Net-(J32-Pad1)") (class "Default")
      (node (ref "J32") (pin "1") (pinfunction "1_1") (pintype "passive"))
      (node (ref "J32") (pin "2") (pinfunction "2_2") (pintype "passive"))
      (node (ref "J32") (pin "3") (pinfunction "3_3") (pintype "passive"))
      (node (ref "J32") (pin "4") (pinfunction "4_4") (pintype "passive"))
      (node (ref "J32") (pin "5") (pinfunction "5_5") (pintype "passive"))
      (node (ref "J32") (pin "6") (pinfunction "6_6") (pintype "passive"))
      (node (ref "J32") (pin "7") (pinfunction "7_7") (pintype "passive"))
    )
    (net (code "27") (name "Net-(J33-Pad1)") (class "Default")
      (node (ref "J33") (pin "1") (pinfunction "1_1") (pintype "passive"))
      (node (ref "J33") (pin "2") (pinfunction "2_2") (pintype "passive"))
      (node (ref "J33") (pin "3") (pinfunction "3_3") (pintype "passive"))
      (node (ref "J33") (pin "4") (pinfunction "4_4") (pintype "passive"))
      (node (ref "J33") (pin "5") (pinfunction "5_5") (pintype "passive"))
      (node (ref "J33") (pin "6") (pinfunction "6_6") (pintype "passive"))
      (node (ref "J33") (pin "7") (pinfunction "7_7") (pintype "passive"))
    )
    (net (code "28") (name "Net-(J34-Pad1)") (class "Default")
      (node (ref "J34") (pin "1") (pinfunction "1_1") (pintype "passive"))
      (node (ref "J34") (pin "2") (pinfunction "2_2") (pintype "passive"))
      (node (ref "J34") (pin "3") (pinfunction "3_3") (pintype "passive"))
      (node (ref "J34") (pin "4") (pinfunction "4_4") (pintype "passive"))
      (node (ref "J34") (pin "5") (pinfunction "5_5") (pintype "passive"))
      (node (ref "J34") (pin "6") (pinfunction "6_6") (pintype "passive"))
      (node (ref "J34") (pin "7") (pinfunction "7_7") (pintype "passive"))
    )
    (net (code "29") (name "Net-(J35-Pad1)") (class "Default")
      (node (ref "J35") (pin "1") (pinfunction "1_1") (pintype "passive"))
      (node (ref "J35") (pin "2") (pinfunction "2_2") (pintype "passive"))
      (node (ref "J35") (pin "3") (pinfunction "3_3") (pintype "passive"))
      (node (ref "J35") (pin "4") (pinfunction "4_4") (pintype "passive"))
      (node (ref "J35") (pin "5") (pinfunction "5_5") (pintype "passive"))
      (node (ref "J35") (pin "6") (pinfunction "6_6") (pintype "passive"))
      (node (ref "J35") (pin "7") (pinfunction "7_7") (pintype "passive"))
    )
    (net (code "30") (name "Net-(J36-Pad1)") (class "Default")
      (node (ref "J36") (pin "1") (pinfunction "1_1") (pintype "passive"))
      (node (ref "J36") (pin "2") (pinfunction "2_2") (pintype "passive"))
      (node (ref "J36") (pin "3") (pinfunction "3_3") (pintype "passive"))
      (node (ref "J36") (pin "4") (pinfunction "4_4") (pintype "passive"))
      (node (ref "J36") (pin "5") (pinfunction "5_5") (pintype "passive"))
      (node (ref "J36") (pin "6") (pinfunction "6_6") (pintype "passive"))
      (node (ref "J36") (pin "7") (pinfunction "7_7") (pintype "passive"))
    )
    (net (code "31") (name "Net-(J37-Pad1)") (class "Default")
      (node (ref "J37") (pin "1") (pinfunction "1_1") (pintype "passive"))
      (node (ref "J37") (pin "2") (pinfunction "2_2") (pintype "passive"))
      (node (ref "J37") (pin "3") (pinfunction "3_3") (pintype "passive"))
      (node (ref "J37") (pin "4") (pinfunction "4_4") (pintype "passive"))
      (node (ref "J37") (pin "5") (pinfunction "5_5") (pintype "passive"))
      (node (ref "J37") (pin "6") (pinfunction "6_6") (pintype "passive"))
      (node (ref "J37") (pin "7") (pinfunction "7_7") (pintype "passive"))
    )
    (net (code "32") (name "Net-(J38-Pad1)") (class "Default")
      (node (ref "J38") (pin "1") (pinfunction "1_1") (pintype "passive"))
      (node (ref "J38") (pin "2") (pinfunction "2_2") (pintype "passive"))
      (node (ref "J38") (pin "3") (pinfunction "3_3") (pintype "passive"))
      (node (ref "J38") (pin "4") (pinfunction "4_4") (pintype "passive"))
      (node (ref "J38") (pin "5") (pinfunction "5_5") (pintype "passive"))
      (node (ref "J38") (pin "6") (pinfunction "6_6") (pintype "passive"))
      (node (ref "J38") (pin "7") (pinfunction "7_7") (pintype "passive"))
    )
    (net (code "33") (name "Net-(J39-Pad1)") (class "Default")
      (node (ref "J39") (pin "1") (pinfunction "1_1") (pintype "passive"))
      (node (ref "J39") (pin "2") (pinfunction "2_2") (pintype "passive"))
      (node (ref "J39") (pin "3") (pinfunction "3_3") (pintype "passive"))
      (node (ref "J39") (pin "4") (pinfunction "4_4") (pintype "passive"))
      (node (ref "J39") (pin "5") (pinfunction "5_5") (pintype "passive"))
      (node (ref "J39") (pin "6") (pinfunction "6_6") (pintype "passive"))
      (node (ref "J39") (pin "7") (pinfunction "7_7") (pintype "passive"))
    )
    (net (code "34") (name "Net-(J40-Pad1)") (class "Default")
      (node (ref "J40") (pin "1") (pinfunction "1_1") (pintype "passive"))
      (node (ref "J40") (pin "2") (pinfunction "2_2") (pintype "passive"))
      (node (ref "J40") (pin "3") (pinfunction "3_3") (pintype "passive"))
      (node (ref "J40") (pin "4") (pinfunction "4_4") (pintype "passive"))
      (node (ref "J40") (pin "5") (pinfunction "5_5") (pintype "passive"))
      (node (ref "J40") (pin "6") (pinfunction "6_6") (pintype "passive"))
      (node (ref "J40") (pin "7") (pinfunction "7_7") (pintype "passive"))
    )
    (net (code "35") (name "Net-(J41-Pad1)") (class "Default")
      (node (ref "J41") (pin "1") (pinfunction "1_1") (pintype "passive"))
      (node (ref "J41") (pin "2") (pinfunction "2_2") (pintype "passive"))
      (node (ref "J41") (pin "3") (pinfunction "3_3") (pintype "passive"))
      (node (ref "J41") (pin "4") (pinfunction "4_4") (pintype "passive"))
      (node (ref "J41") (pin "5") (pinfunction "5_5") (pintype "passive"))
      (node (ref "J41") (pin "6") (pinfunction "6_6") (pintype "passive"))
      (node (ref "J41") (pin "7") (pinfunction "7_7") (pintype "passive"))
    )
    (net (code "36") (name "Net-(J42-Pad1)") (class "Default")
      (node (ref "J42") (pin "1") (pinfunction "1_1") (pintype "passive"))
      (node (ref "J42") (pin "2") (pinfunction "2_2") (pintype "passive"))
      (node (ref "J42") (pin "3") (pinfunction "3_3") (pintype "passive"))
      (node (ref "J42") (pin "4") (pinfunction "4_4") (pintype "passive"))
      (node (ref "J42") (pin "5") (pinfunction "5_5") (pintype "passive"))
      (node (ref "J42") (pin "6") (pinfunction "6_6") (pintype "passive"))
      (node (ref "J42") (pin "7") (pinfunction "7_7") (pintype "passive"))
    )
    (net (code "37") (name "Net-(J43-Pad1)") (class "Default")
      (node (ref "J43") (pin "1") (pinfunction "1_1") (pintype "passive"))
      (node (ref "J43") (pin "2") (pinfunction "2_2") (pintype "passive"))
      (node (ref "J43") (pin "3") (pinfunction "3_3") (pintype "passive"))
      (node (ref "J43") (pin "4") (pinfunction "4_4") (pintype "passive"))
      (node (ref "J43") (pin "5") (pinfunction "5_5") (pintype "passive"))
      (node (ref "J43") (pin "6") (pinfunction "6_6") (pintype "passive"))
      (node (ref "J43") (pin "7") (pinfunction "7_7") (pintype "passive"))
    )
    (net (code "38") (name "Net-(J44-Pad1)") (class "Default")
      (node (ref "J44") (pin "1") (pinfunction "1_1") (pintype "passive"))
      (node (ref "J44") (pin "2") (pinfunction "2_2") (pintype "passive"))
      (node (ref "J44") (pin "3") (pinfunction "3_3") (pintype "passive"))
      (node (ref "J44") (pin "4") (pinfunction "4_4") (pintype "passive"))
      (node (ref "J44") (pin "5") (pinfunction "5_5") (pintype "passive"))
      (node (ref "J44") (pin "6") (pinfunction "6_6") (pintype "passive"))
      (node (ref "J44") (pin "7") (pinfunction "7_7") (pintype "passive"))
    )
    (net (code "39") (name "Net-(J45-Pad1)") (class "Default")
      (node (ref "J45") (pin "1") (pinfunction "1_1") (pintype "passive"))
      (node (ref "J45") (pin "2") (pinfunction "2_2") (pintype "passive"))
      (node (ref "J45") (pin "3") (pinfunction "3_3") (pintype "passive"))
      (node (ref "J45") (pin "4") (pinfunction "4_4") (pintype "passive"))
      (node (ref "J45") (pin "5") (pinfunction "5_5") (pintype "passive"))
      (node (ref "J45") (pin "6") (pinfunction "6_6") (pintype "passive"))
      (node (ref "J45") (pin "7") (pinfunction "7_7") (pintype "passive"))
    )
    (net (code "40") (name "Net-(J46-Pad1)") (class "Default")
      (node (ref "J46") (pin "1") (pinfunction "1_1") (pintype "passive"))
      (node (ref "J46") (pin "2") (pinfunction "2_2") (pintype "passive"))
      (node (ref "J46") (pin "3") (pinfunction "3_3") (pintype "passive"))
      (node (ref "J46") (pin "4") (pinfunction "4_4") (pintype "passive"))
      (node (ref "J46") (pin "5") (pinfunction "5_5") (pintype "passive"))
      (node (ref "J46") (pin "6") (pinfunction "6_6") (pintype "passive"))
      (node (ref "J46") (pin "7") (pinfunction "7_7") (pintype "passive"))
    )
    (net (code "41") (name "Net-(J47-Pad1)") (class "Default")
      (node (ref "J47") (pin "1") (pinfunction "1_1") (pintype "passive"))
      (node (ref "J47") (pin "2") (pinfunction "2_2") (pintype "passive"))
      (node (ref "J47") (pin "3") (pinfunction "3_3") (pintype "passive"))
      (node (ref "J47") (pin "4") (pinfunction "4_4") (pintype "passive"))
      (node (ref "J47") (pin "5") (pinfunction "5_5") (pintype "passive"))
      (node (ref "J47") (pin "6") (pinfunction "6_6") (pintype "passive"))
      (node (ref "J47") (pin "7") (pinfunction "7_7") (pintype "passive"))
    )
    (net (code "42") (name "Net-(J48-Pad1)") (class "Default")
      (node (ref "J48") (pin "1") (pinfunction "1_1") (pintype "passive"))
      (node (ref "J48") (pin "2") (pinfunction "2_2") (pintype "passive"))
      (node (ref "J48") (pin "3") (pinfunction "3_3") (pintype "passive"))
      (node (ref "J48") (pin "4") (pinfunction "4_4") (pintype "passive"))
      (node (ref "J48") (pin "5") (pinfunction "5_5") (pintype "passive"))
      (node (ref "J48") (pin "6") (pinfunction "6_6") (pintype "passive"))
      (node (ref "J48") (pin "7") (pinfunction "7_7") (pintype "passive"))
    )
    (net (code "43") (name "Net-(J49-Pad1)") (class "Default")
      (node (ref "J49") (pin "1") (pinfunction "1_1") (pintype "passive"))
      (node (ref "J49") (pin "2") (pinfunction "2_2") (pintype "passive"))
      (node (ref "J49") (pin "3") (pinfunction "3_3") (pintype "passive"))
      (node (ref "J49") (pin "4") (pinfunction "4_4") (pintype "passive"))
      (node (ref "J49") (pin "5") (pinfunction "5_5") (pintype "passive"))
      (node (ref "J49") (pin "6") (pinfunction "6_6") (pintype "passive"))
      (node (ref "J49") (pin "7") (pinfunction "7_7") (pintype "passive"))
    )
    (net (code "44") (name "Net-(J50-Pad1)") (class "Default")
      (node (ref "J50") (pin "1") (pinfunction "1_1") (pintype "passive"))
      (node (ref "J50") (pin "2") (pinfunction "2_2") (pintype "passive"))
      (node (ref "J50") (pin "3") (pinfunction "3_3") (pintype "passive"))
      (node (ref "J50") (pin "4") (pinfunction "4_4") (pintype "passive"))
      (node (ref "J50") (pin "5") (pinfunction "5_5") (pintype "passive"))
      (node (ref "J50") (pin "6") (pinfunction "6_6") (pintype "passive"))
      (node (ref "J50") (pin "7") (pinfunction "7_7") (pintype "passive"))
    )
    (net (code "45") (name "Net-(J51-Pad1)") (class "Default")
      (node (ref "J51") (pin "1") (pinfunction "1_1") (pintype "passive"))
      (node (ref "J51") (pin "2") (pinfunction "2_2") (pintype "passive"))
      (node (ref "J51") (pin "3") (pinfunction "3_3") (pintype "passive"))
      (node (ref "J51") (pin "4") (pinfunction "4_4") (pintype "passive"))
      (node (ref "J51") (pin "5") (pinfunction "5_5") (pintype "passive"))
      (node (ref "J51") (pin "6") (pinfunction "6_6") (pintype "passive"))
      (node (ref "J51") (pin "7") (pinfunction "7_7") (pintype "passive"))
    )
    (net (code "46") (name "Net-(J52-Pad1)") (class "Default")
      (node (ref "J52") (pin "1") (pinfunction "1_1") (pintype "passive"))
      (node (ref "J52") (pin "2") (pinfunction "2_2") (pintype "passive"))
      (node (ref "J52") (pin "3") (pinfunction "3_3") (pintype "passive"))
      (node (ref "J52") (pin "4") (pinfunction "4_4") (pintype "passive"))
      (node (ref "J52") (pin "5") (pinfunction "5_5") (pintype "passive"))
      (node (ref "J52") (pin "6") (pinfunction "6_6") (pintype "passive"))
      (node (ref "J52") (pin "7") (pinfunction "7_7") (pintype "passive"))
    )
    (net (code "47") (name "Net-(J53-Pad1)") (class "Default")
      (node (ref "J53") (pin "1") (pinfunction "1_1") (pintype "passive"))
      (node (ref "J53") (pin "2") (pinfunction "2_2") (pintype "passive"))
      (node (ref "J53") (pin "3") (pinfunction "3_3") (pintype "passive"))
      (node (ref "J53") (pin "4") (pinfunction "4_4") (pintype "passive"))
      (node (ref "J53") (pin "5") (pinfunction "5_5") (pintype "passive"))
      (node (ref "J53") (pin "6") (pinfunction "6_6") (pintype "passive"))
      (node (ref "J53") (pin "7") (pinfunction "7_7") (pintype "passive"))
    )
    (net (code "48") (name "Net-(J54-Pad1)") (class "Default")
      (node (ref "J54") (pin "1") (pinfunction "1_1") (pintype "passive"))
      (node (ref "J54") (pin "2") (pinfunction "2_2") (pintype "passive"))
      (node (ref "J54") (pin "3") (pinfunction "3_3") (pintype "passive"))
      (node (ref "J54") (pin "4") (pinfunction "4_4") (pintype "passive"))
      (node (ref "J54") (pin "5") (pinfunction "5_5") (pintype "passive"))
      (node (ref "J54") (pin "6") (pinfunction "6_6") (pintype "passive"))
      (node (ref "J54") (pin "7") (pinfunction "7_7") (pintype "passive"))
    )
    (net (code "49") (name "Net-(J55-Pad1)") (class "Default")
      (node (ref "J55") (pin "1") (pinfunction "1_1") (pintype "passive"))
      (node (ref "J55") (pin "2") (pinfunction "2_2") (pintype "passive"))
      (node (ref "J55") (pin "3") (pinfunction "3_3") (pintype "passive"))
      (node (ref "J55") (pin "4") (pinfunction "4_4") (pintype "passive"))
      (node (ref "J55") (pin "5") (pinfunction "5_5") (pintype "passive"))
      (node (ref "J55") (pin "6") (pinfunction "6_6") (pintype "passive"))
      (node (ref "J55") (pin "7") (pinfunction "7_7") (pintype "passive"))
    )
    (net (code "50") (name "Net-(J56-Pad1)") (class "Default")
      (node (ref "J56") (pin "1") (pinfunction "1_1") (pintype "passive"))
      (node (ref "J56") (pin "2") (pinfunction "2_2") (pintype "passive"))
      (node (ref "J56") (pin "3") (pinfunction "3_3") (pintype "passive"))
      (node (ref "J56") (pin "4") (pinfunction "4_4") (pintype "passive"))
      (node (ref "J56") (pin "5") (pinfunction "5_5") (pintype "passive"))
      (node (ref "J56") (pin "6") (pinfunction "6_6") (pintype "passive"))
      (node (ref "J56") (pin "7") (pinfunction "7_7") (pintype "passive"))
    )
    (net (code "51") (name "Net-(J57-Pad1)") (class "Default")
      (node (ref "J57") (pin "1") (pinfunction "1_1") (pintype "passive"))
      (node (ref "J57") (pin "2") (pinfunction "2_2") (pintype "passive"))
      (node (ref "J57") (pin "3") (pinfunction "3_3") (pintype "passive"))
      (node (ref "J57") (pin "4") (pinfunction "4_4") (pintype "passive"))
      (node (ref "J57") (pin "5") (pinfunction "5_5") (pintype "passive"))
      (node (ref "J57") (pin "6") (pinfunction "6_6") (pintype "passive"))
      (node (ref "J57") (pin "7") (pinfunction "7_7") (pintype "passive"))
    )
    (net (code "52") (name "Net-(J58-Pad1)") (class "Default")
      (node (ref "J58") (pin "1") (pinfunction "1_1") (pintype "passive"))
      (node (ref "J58") (pin "2") (pinfunction "2_2") (pintype "passive"))
      (node (ref "J58") (pin "3") (pinfunction "3_3") (pintype "passive"))
      (node (ref "J58") (pin "4") (pinfunction "4_4") (pintype "passive"))
      (node (ref "J58") (pin "5") (pinfunction "5_5") (pintype "passive"))
      (node (ref "J58") (pin "6") (pinfunction "6_6") (pintype "passive"))
      (node (ref "J58") (pin "7") (pinfunction "7_7") (pintype "passive"))
    )
    (net (code "53") (name "Net-(J59-Pad1)") (class "Default")
      (node (ref "J59") (pin "1") (pinfunction "1_1") (pintype "passive"))
      (node (ref "J59") (pin "2") (pinfunction "2_2") (pintype "passive"))
      (node (ref "J59") (pin "3") (pinfunction "3_3") (pintype "passive"))
      (node (ref "J59") (pin "4") (pinfunction "4_4") (pintype "passive"))
      (node (ref "J59") (pin "5") (pinfunction "5_5") (pintype "passive"))
      (node (ref "J59") (pin "6") (pinfunction "6_6") (pintype "passive"))
      (node (ref "J59") (pin "7") (pinfunction "7_7") (pintype "passive"))
    )
    (net (code "54") (name "Net-(J60-Pad1)") (class "Default")
      (node (ref "J60") (pin "1") (pinfunction "1_1") (pintype "passive"))
      (node (ref "J60") (pin "2") (pinfunction "2_2") (pintype "passive"))
      (node (ref "J60") (pin "3") (pinfunction "3_3") (pintype "passive"))
      (node (ref "J60") (pin "4") (pinfunction "4_4") (pintype "passive"))
      (node (ref "J60") (pin "5") (pinfunction "5_5") (pintype "passive"))
      (node (ref "J60") (pin "6") (pinfunction "6_6") (pintype "passive"))
    )
    (net (code "55") (name "VCC") (class "Default")
      (node (ref "DC") (pin "1") (pinfunction "VIN_1") (pintype "passive"))
      (node (ref "J1") (pin "1") (pinfunction "1_1") (pintype "passive"))
      (node (ref "U2") (pin "1") (pinfunction "IN_1") (pintype "input"))
      (node (ref "U2") (pin "3") (pinfunction "EN_3") (pintype "input"))
      (node (ref "X1") (pin "VBUS") (pinfunction "VBUS_VBUS") (pintype "power_in"))
    )
    (net (code "56") (name "VDD") (class "Default")
      (node (ref "DC") (pin "3") (pinfunction "VOUT_3") (pintype "passive"))
      (node (ref "J3") (pin "1") (pinfunction "1_1") (pintype "passive"))
      (node (ref "J3") (pin "10") (pinfunction "10_10") (pintype "passive"))
      (node (ref "J3") (pin "11") (pinfunction "11_11") (pintype "passive"))
      (node (ref "J3") (pin "12") (pinfunction "12_12") (pintype "passive"))
      (node (ref "J3") (pin "13") (pinfunction "13_13") (pintype "passive"))
      (node (ref "J3") (pin "14") (pinfunction "14_14") (pintype "passive"))
      (node (ref "J3") (pin "15") (pinfunction "15_15") (pintype "passive"))
      (node (ref "J3") (pin "16") (pinfunction "16_16") (pintype "passive"))
      (node (ref "J3") (pin "17") (pinfunction "17_17") (pintype "passive"))
      (node (ref "J3") (pin "18") (pinfunction "18_18") (pintype "passive"))
      (node (ref "J3") (pin "19") (pinfunction "19_19") (pintype "passive"))
      (node (ref "J3") (pin "2") (pinfunction "2_2") (pintype "passive"))
      (node (ref "J3") (pin "20") (pinfunction "20_20") (pintype "passive"))
      (node (ref "J3") (pin "21") (pinfunction "21_21") (pintype "passive"))
      (node (ref "J3") (pin "22") (pinfunction "22_22") (pintype "passive"))
      (node (ref "J3") (pin "23") (pinfunction "23_23") (pintype "passive"))
      (node (ref "J3") (pin "24") (pinfunction "24_24") (pintype "passive"))
      (node (ref "J3") (pin "25") (pinfunction "25_25") (pintype "passive"))
      (node (ref "J3") (pin "26") (pinfunction "26_26") (pintype "passive"))
      (node (ref "J3") (pin "27") (pinfunction "27_27") (pintype "passive"))
      (node (ref "J3") (pin "28") (pinfunction "28_28") (pintype "passive"))
      (node (ref "J3") (pin "29") (pinfunction "29_29") (pintype "passive"))
      (node (ref "J3") (pin "3") (pinfunction "3_3") (pintype "passive"))
      (node (ref "J3") (pin "4") (pinfunction "4_4") (pintype "passive"))
      (node (ref "J3") (pin "5") (pinfunction "5_5") (pintype "passive"))
      (node (ref "J3") (pin "6") (pinfunction "6_6") (pintype "passive"))
      (node (ref "J3") (pin "7") (pinfunction "7_7") (pintype "passive"))
      (node (ref "J3") (pin "8") (pinfunction "8_8") (pintype "passive"))
      (node (ref "J3") (pin "9") (pinfunction "9_9") (pintype "passive"))
      (node (ref "J5") (pin "1") (pinfunction "1_1") (pintype "passive"))
      (node (ref "J5") (pin "10") (pinfunction "10_10") (pintype "passive"))
      (node (ref "J5") (pin "11") (pinfunction "11_11") (pintype "passive"))
      (node (ref "J5") (pin "12") (pinfunction "12_12") (pintype "passive"))
      (node (ref "J5") (pin "13") (pinfunction "13_13") (pintype "passive"))
      (node (ref "J5") (pin "14") (pinfunction "14_14") (pintype "passive"))
      (node (ref "J5") (pin "15") (pinfunction "15_15") (pintype "passive"))
      (node (ref "J5") (pin "16") (pinfunction "16_16") (pintype "passive"))
      (node (ref "J5") (pin "17") (pinfunction "17_17") (pintype "passive"))
      (node (ref "J5") (pin "18") (pinfunction "18_18") (pintype "passive"))
      (node (ref "J5") (pin "19") (pinfunction "19_19") (pintype "passive"))
      (node (ref "J5") (pin "2") (pinfunction "2_2") (pintype "passive"))
      (node (ref "J5") (pin "20") (pinfunction "20_20") (pintype "passive"))
      (node (ref "J5") (pin "3") (pinfunction "3_3") (pintype "passive"))
      (node (ref "J5") (pin "4") (pinfunction "4_4") (pintype "passive"))
      (node (ref "J5") (pin "5") (pinfunction "5_5") (pintype "passive"))
      (node (ref "J5") (pin "6") (pinfunction "6_6") (pintype "passive"))
      (node (ref "J5") (pin "7") (pinfunction "7_7") (pintype "passive"))
      (node (ref "J5") (pin "8") (pinfunction "8_8") (pintype "passive"))
      (node (ref "J5") (pin "9") (pinfunction "9_9") (pintype "passive"))
      (node (ref "J7") (pin "1") (pinfunction "1_1") (pintype "passive"))
      (node (ref "J7") (pin "2") (pinfunction "2_2") (pintype "passive"))
      (node (ref "J7") (pin "3") (pinfunction "3_3") (pintype "passive"))
      (node (ref "J7") (pin "4") (pinfunction "4_4") (pintype "passive"))
      (node (ref "J7") (pin "5") (pinfunction "5_5") (pintype "passive"))
      (node (ref "U2") (pin "5") (pinfunction "OUT_5") (pintype "passive"))
    )
    (net (code "57") (name "unconnected-(U2-BP-Pad4)") (class "Default")
      (node (ref "U2") (pin "4") (pinfunction "BP_4") (pintype "input"))
    )
    (net (code "58") (name "unconnected-(X1-PadD+)") (class "Default")
      (node (ref "X1") (pin "D+") (pinfunction "D+_D+") (pintype "bidirectional"))
    )
    (net (code "59") (name "unconnected-(X1-PadD-)") (class "Default")
      (node (ref "X1") (pin "D-") (pinfunction "D-_D-") (pintype "bidirectional"))
    )
    (net (code "60") (name "unconnected-(X1-PadID)") (class "Default")
      (node (ref "X1") (pin "ID") (pinfunction "ID_ID") (pintype "bidirectional"))
    )
  )
)
